# OSP_Carrier_V8_SD.net
KiCad netlist of a schematic drawn in Altium Designer
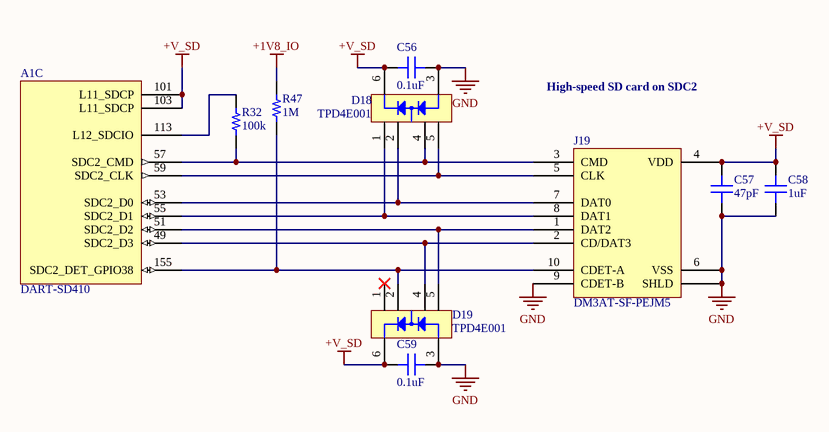
[diagram p0: OSP_Carrier_V8_SD.SchDoc]

(export (version "E")
  (design (tool "Eeschema 10.0.6"))
  (components
    (comp (ref "A1")
      (value "DART-SD410")
      (footprint "DART-SD410")
      (description "Variscite DART-SD410 System on Module")
      (libsource (lib "DART-SD410") (part "DART-SD410"))
    )
    (comp (ref "C56")
      (value "0.1uF")
      (footprint "CAP 0402/1005")
      (description "CAP CER 0.1UF 50V X7R 0402")
      (fields
        (field (name "PART NUMBER") "C1005X7R1H104K050BB")
        (field (name "MANUFACTURER") "TDK Corporation")
      )
      (libsource (lib "Celestial Library Database") (part "Capacitor"))
    )
    (comp (ref "C57")
      (value "47pF")
      (footprint "CAP 0402/1005")
      (description "CAP CER 47PF 50V C0G 0402")
      (fields
        (field (name "PART NUMBER") "C1005C0G1H470G050BA")
        (field (name "MANUFACTURER") "TDK Corporation")
      )
      (libsource (lib "Celestial Library Database") (part "Capacitor"))
    )
    (comp (ref "C58")
      (value "1uF")
      (footprint "CAP 0603/1608")
      (description "CAP CER 1UF 25V X7R 0603")
      (fields
        (field (name "PART NUMBER") "C1608X7R1E105K080AB")
        (field (name "MANUFACTURER") "TDK Corporation")
      )
      (libsource (lib "Celestial Library Database") (part "Capacitor"))
    )
    (comp (ref "C59")
      (value "0.1uF")
      (footprint "CAP 0402/1005")
      (description "CAP CER 0.1UF 50V X7R 0402")
      (fields
        (field (name "PART NUMBER") "C1005X7R1H104K050BB")
        (field (name "MANUFACTURER") "TDK Corporation")
      )
      (libsource (lib "Celestial Library Database") (part "Capacitor"))
    )
    (comp (ref "D18")
      (value "TPD4E001")
      (footprint "TI_SOT-563_DRL")
      (description "TI TPD4E001 4-channel TVS ESD protection diodes")
      (libsource (lib "") (part "TI_TPD4E001_1"))
    )
    (comp (ref "D19")
      (value "TPD4E001")
      (footprint "TI_SOT-563_DRL")
      (description "TI TPD4E001 4-channel TVS ESD protection diodes")
      (libsource (lib "OSP_Symbols") (part "TI_TPD4E001"))
    )
    (comp (ref "J19")
      (value "DM3AT-SF-PEJM5")
      (footprint "HIROSE DM3AT-SF-PEJM5")
      (description "CONN MICRO SD CARD PUSH-PUSH R/A")
      (fields (field (name "MANUFACTURER") "Hirose Electric Co Ltd"))
      (libsource (lib "Celestial Library Database") (part "Hirose DM3 MicroSD"))
    )
    (comp (ref "R32")
      (value "100k")
      (footprint "RES 0402/1005")
      (description "RES SMD 100K OHM 1% 1/10W 0402")
      (fields (field (name "PART NUMBER") "ERJ-2RKF1003X"))
      (libsource (lib "Celestial Library Database") (part "Resistor"))
    )
    (comp (ref "R47")
      (value "1M")
      (footprint "RES 0402/1005")
      (description "RES SMD 1M OHM 1% 1/10W 0402")
      (fields
        (field (name "PART NUMBER") "ERJ-2RKF1004X")
        (field (name "MANUFACTURER") "Panasonic Electronic Components")
      )
      (libsource (lib "Celestial Library Database") (part "Resistor"))
    )
  )
  (nets
    (net (code "1") (name "+1V8_IO") (class "Default")
      (node (ref "R47") (pin "2") (pinfunction "2_2") (pintype "passive"))
    )
    (net (code "2") (name "+V_SD") (class "Default")
      (node (ref "A1") (pin "101") (pinfunction "L11_SDCP_101") (pintype "power_in"))
      (node (ref "A1") (pin "103") (pinfunction "L11_SDCP_103") (pintype "power_in"))
      (node (ref "C56") (pin "2") (pinfunction "2_2") (pintype "passive"))
      (node (ref "C57") (pin "2") (pinfunction "2_2") (pintype "passive"))
      (node (ref "C58") (pin "2") (pinfunction "2_2") (pintype "passive"))
      (node (ref "C59") (pin "2") (pinfunction "2_2") (pintype "passive"))
      (node (ref "D18") (pin "6") (pintype "power_in"))
      (node (ref "D19") (pin "6") (pintype "power_in"))
      (node (ref "J19") (pin "4") (pinfunction "VDD_4") (pintype "passive"))
    )
    (net (code "3") (name "GND") (class "Default")
      (node (ref "C56") (pin "1") (pinfunction "1_1") (pintype "passive"))
      (node (ref "C57") (pin "1") (pinfunction "1_1") (pintype "passive"))
      (node (ref "C58") (pin "1") (pinfunction "1_1") (pintype "passive"))
      (node (ref "C59") (pin "1") (pinfunction "1_1") (pintype "passive"))
      (node (ref "D18") (pin "3") (pintype "power_in"))
      (node (ref "D19") (pin "3") (pintype "power_in"))
      (node (ref "J19") (pin "6") (pinfunction "VSS_6") (pintype "passive"))
      (node (ref "J19") (pin "9") (pinfunction "CDET-B_9") (pintype "passive"))
      (node (ref "J19") (pin "S") (pinfunction "SHLD_S") (pintype "passive"))
    )
    (net (code "4") (name "Net-(A1C-L12_SDCIO)") (class "Default")
      (node (ref "A1") (pin "113") (pinfunction "L12_SDCIO_113") (pintype "power_in"))
      (node (ref "R32") (pin "2") (pinfunction "2_2") (pintype "passive"))
    )
    (net (code "5") (name "Net-(A1C-SDC2_CLK)") (class "Default")
      (node (ref "A1") (pin "59") (pinfunction "SDC2_CLK_59") (pintype "output"))
      (node (ref "D18") (pin "5") (pintype "passive"))
      (node (ref "J19") (pin "5") (pinfunction "CLK_5") (pintype "passive"))
    )
    (net (code "6") (name "Net-(A1C-SDC2_CMD)") (class "Default")
      (node (ref "A1") (pin "57") (pinfunction "SDC2_CMD_57") (pintype "output"))
      (node (ref "D18") (pin "4") (pintype "passive"))
      (node (ref "J19") (pin "3") (pinfunction "CMD_3") (pintype "passive"))
      (node (ref "R32") (pin "1") (pinfunction "1_1") (pintype "passive"))
    )
    (net (code "7") (name "Net-(A1C-SDC2_D0)") (class "Default")
      (node (ref "A1") (pin "53") (pinfunction "SDC2_D0_53") (pintype "bidirectional"))
      (node (ref "D18") (pin "2") (pintype "passive"))
      (node (ref "J19") (pin "7") (pinfunction "DAT0_7") (pintype "passive"))
    )
    (net (code "8") (name "Net-(A1C-SDC2_D1)") (class "Default")
      (node (ref "A1") (pin "55") (pinfunction "SDC2_D1_55") (pintype "bidirectional"))
      (node (ref "D18") (pin "1") (pintype "passive"))
      (node (ref "J19") (pin "8") (pinfunction "DAT1_8") (pintype "passive"))
    )
    (net (code "9") (name "Net-(A1C-SDC2_D2)") (class "Default")
      (node (ref "A1") (pin "51") (pinfunction "SDC2_D2_51") (pintype "bidirectional"))
      (node (ref "D19") (pin "5") (pintype "passive"))
      (node (ref "J19") (pin "1") (pinfunction "DAT2_1") (pintype "passive"))
    )
    (net (code "10") (name "Net-(A1C-SDC2_D3)") (class "Default")
      (node (ref "A1") (pin "49") (pinfunction "SDC2_D3_49") (pintype "bidirectional"))
      (node (ref "D19") (pin "4") (pintype "passive"))
      (node (ref "J19") (pin "2") (pinfunction "CD/DAT3_2") (pintype "passive"))
    )
    (net (code "11") (name "Net-(A1C-SDC2_DET_GPIO38)") (class "Default")
      (node (ref "A1") (pin "155") (pinfunction "SDC2_DET_GPIO38_155") (pintype "bidirectional"))
      (node (ref "D19") (pin "2") (pintype "passive"))
      (node (ref "J19") (pin "10") (pinfunction "CDET-A_10") (pintype "passive"))
      (node (ref "R47") (pin "1") (pinfunction "1_1") (pintype "passive"))
    )
    (net (code "12") (name "unconnected-(D19-Pad1)") (class "Default")
      (node (ref "D19") (pin "1") (pintype "passive+no_connect"))
    )
  )
)
